# PANOBOT_MAIN_V2.net
KiCad netlist of a schematic drawn in EAGLE
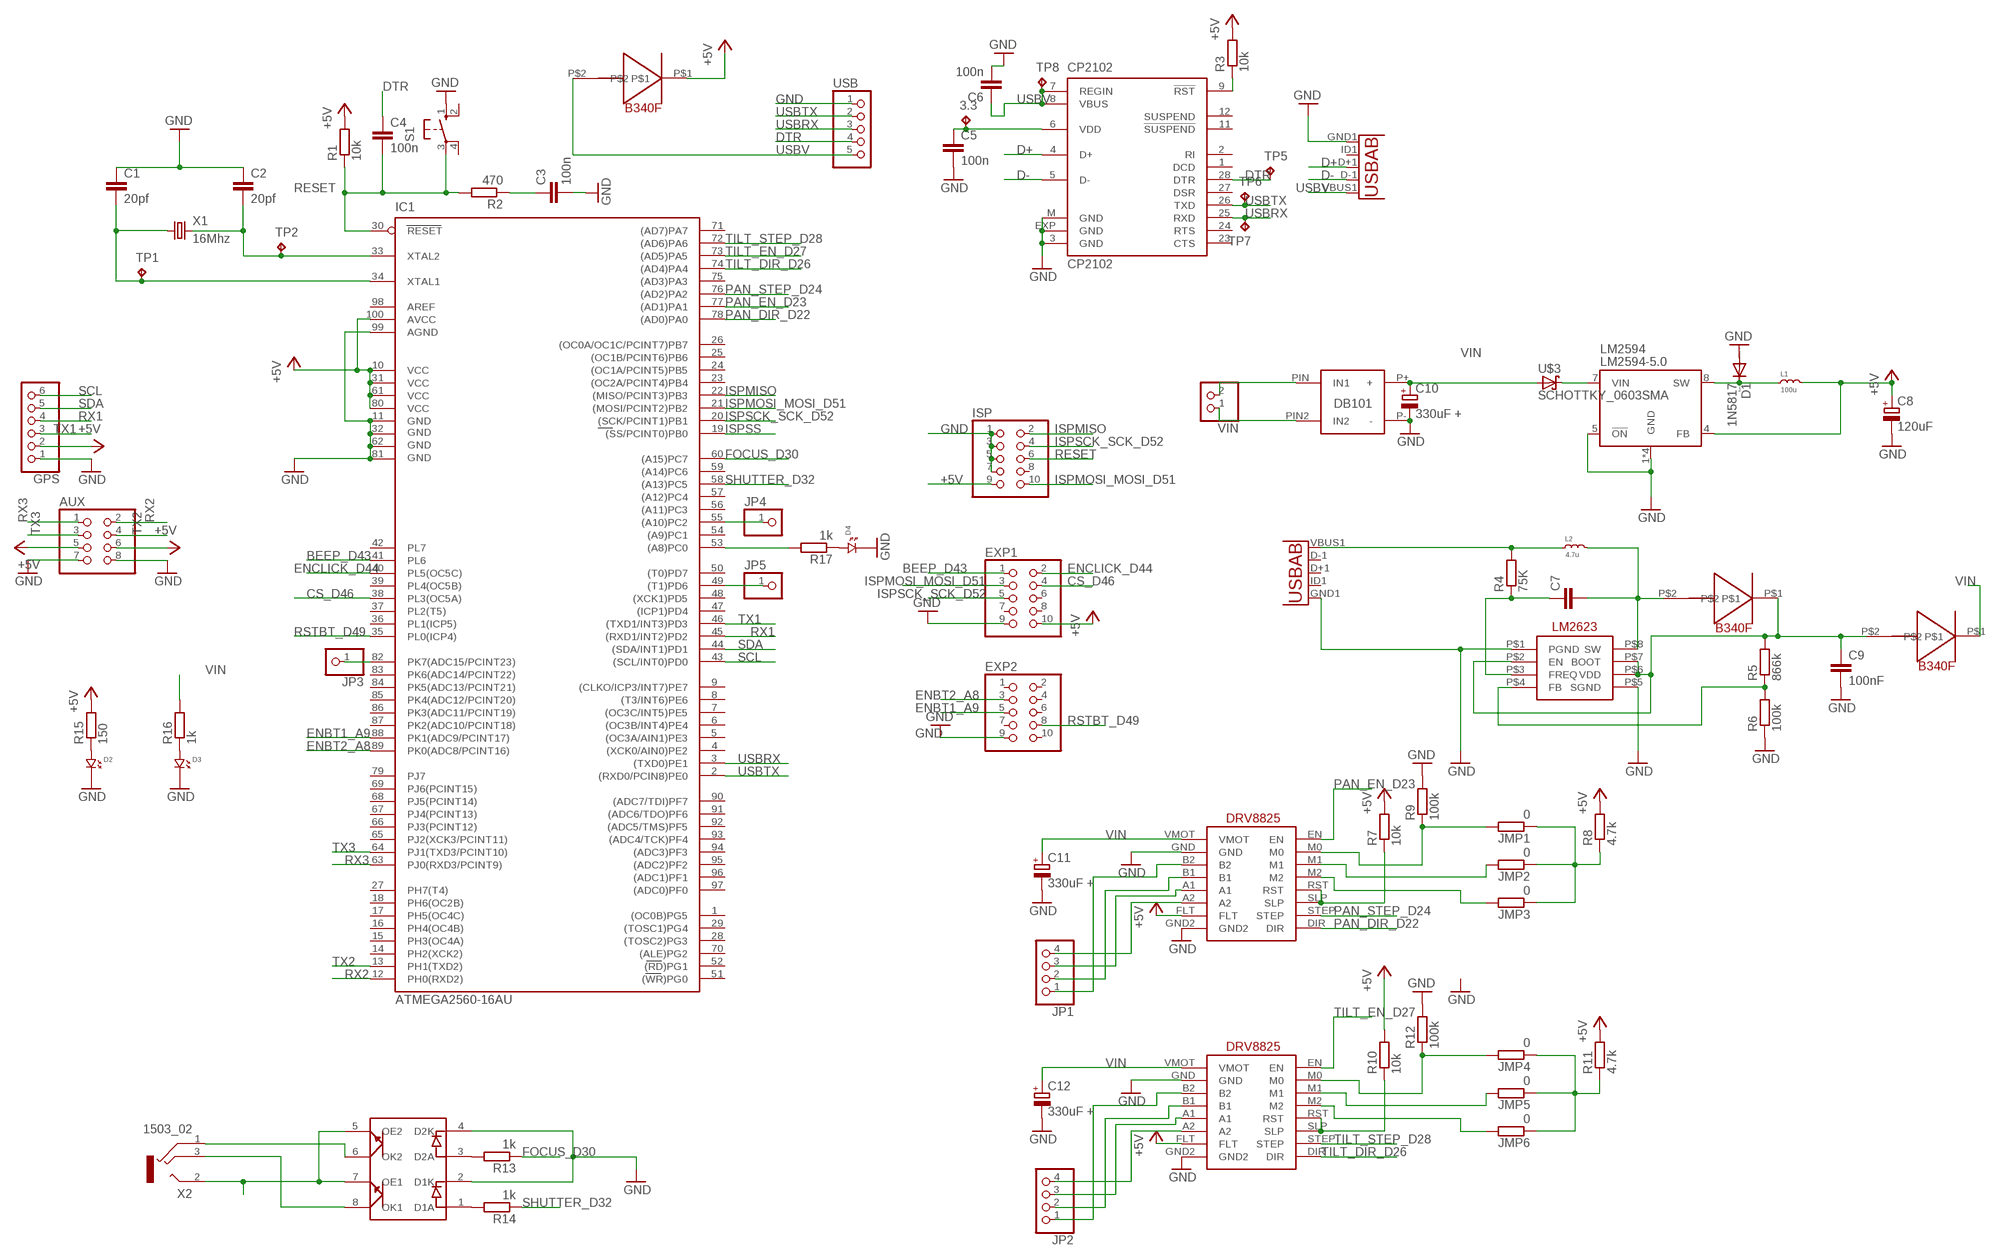
[diagram p0: schematic, sheet 1]

(export (version "E")
  (design (tool "Eeschema 10.0.6"))
  (components
    (comp (ref "3.3")
      (value "TPTP16R")
      (footprint "eagle-import:TP16R")
      (libsource (lib "eagle-import") (part "TPTP16R"))
    )
    (comp (ref "AUX")
      (value "PINHD-2X4")
      (footprint "eagle-import:2X04")
      (libsource (lib "eagle-import") (part "PINHD-2X4"))
    )
    (comp (ref "C1")
      (value "20pf")
      (footprint "eagle-import:C0603K")
      (libsource (lib "eagle-import") (part "C-EUC0603K"))
    )
    (comp (ref "C2")
      (value "20pf")
      (footprint "eagle-import:C0603K")
      (libsource (lib "eagle-import") (part "C-EUC0603K"))
    )
    (comp (ref "C3")
      (value "100n")
      (footprint "eagle-import:C0805")
      (libsource (lib "eagle-import") (part "C-EUC0805"))
    )
    (comp (ref "C4")
      (value "100n")
      (footprint "eagle-import:C0805")
      (libsource (lib "eagle-import") (part "C-EUC0805"))
    )
    (comp (ref "C5")
      (value "100n")
      (footprint "eagle-import:C0805")
      (libsource (lib "eagle-import") (part "C-EUC0805"))
    )
    (comp (ref "C6")
      (value "100n")
      (footprint "eagle-import:C0805")
      (libsource (lib "eagle-import") (part "C-EUC0805"))
    )
    (comp (ref "C7")
      (value "C-EUC0603")
      (footprint "eagle-import:C0603")
      (libsource (lib "eagle-import") (part "C-EUC0603"))
    )
    (comp (ref "C8")
      (value "120uF")
      (footprint "eagle-import:153CLV-0605")
      (libsource (lib "eagle-import") (part "CPOL-EU153CLV-0605"))
    )
    (comp (ref "C9")
      (value "100nF")
      (footprint "eagle-import:C025-030X050")
      (libsource (lib "eagle-import") (part "C-EU025-030X050"))
    )
    (comp (ref "C10")
      (value "330uF +")
      (footprint "eagle-import:SANYO-OSCON_F13")
      (libsource (lib "eagle-import") (part "CPOL-EUSANYO_F13"))
    )
    (comp (ref "C11")
      (value "330uF +")
      (footprint "eagle-import:SANYO-OSCON_F13")
      (libsource (lib "eagle-import") (part "CPOL-EUSANYO_F13"))
    )
    (comp (ref "C12")
      (value "330uF +")
      (footprint "eagle-import:SANYO-OSCON_F13")
      (libsource (lib "eagle-import") (part "CPOL-EUSANYO_F13"))
    )
    (comp (ref "CP2102")
      (value "CP2102")
      (footprint "eagle-import:MLP28")
      (fields (field (name "MF") "FARNELL") (field (name "MPN") "CP2102-GM"))
      (libsource (lib "eagle-import") (part "CP2102"))
    )
    (comp (ref "D1")
      (value "1N5817")
      (footprint "eagle-import:DO41-10")
      (libsource (lib "eagle-import") (part "1N4942"))
    )
    (comp (ref "D2")
      (value "LED.0805")
      (footprint "eagle-import:0805.LED")
      (libsource (lib "eagle-import") (part "LED.0805"))
    )
    (comp (ref "D3")
      (value "LED.0805")
      (footprint "eagle-import:0805.LED")
      (libsource (lib "eagle-import") (part "LED.0805"))
    )
    (comp (ref "D4")
      (value "LED.0805")
      (footprint "eagle-import:0805.LED")
      (libsource (lib "eagle-import") (part "LED.0805"))
    )
    (comp (ref "EXP1")
      (value "PINHD-2X5")
      (footprint "eagle-import:2X05")
      (libsource (lib "eagle-import") (part "PINHD-2X5"))
    )
    (comp (ref "EXP2")
      (value "PINHD-2X5")
      (footprint "eagle-import:2X05")
      (libsource (lib "eagle-import") (part "PINHD-2X5"))
    )
    (comp (ref "GPS")
      (value "PINHD-1X6")
      (footprint "eagle-import:1X06")
      (libsource (lib "eagle-import") (part "PINHD-1X6"))
    )
    (comp (ref "IC1")
      (value "ATMEGA2560-16AU")
      (footprint "eagle-import:TQFP100")
      (libsource (lib "eagle-import") (part "ATMEGAAU2560-16"))
    )
    (comp (ref "ISP")
      (value "PINHD-2X5")
      (footprint "eagle-import:2X05")
      (libsource (lib "eagle-import") (part "PINHD-2X5"))
    )
    (comp (ref "JMP1")
      (value "0")
      (footprint "eagle-import:R0805")
      (libsource (lib "eagle-import") (part "R-EU_R0805"))
    )
    (comp (ref "JMP2")
      (value "0")
      (footprint "eagle-import:R0805")
      (libsource (lib "eagle-import") (part "R-EU_R0805"))
    )
    (comp (ref "JMP3")
      (value "0")
      (footprint "eagle-import:R0805")
      (libsource (lib "eagle-import") (part "R-EU_R0805"))
    )
    (comp (ref "JMP4")
      (value "0")
      (footprint "eagle-import:R0805")
      (libsource (lib "eagle-import") (part "R-EU_R0805"))
    )
    (comp (ref "JMP5")
      (value "0")
      (footprint "eagle-import:R0805")
      (libsource (lib "eagle-import") (part "R-EU_R0805"))
    )
    (comp (ref "JMP6")
      (value "0")
      (footprint "eagle-import:R0805")
      (libsource (lib "eagle-import") (part "R-EU_R0805"))
    )
    (comp (ref "JP1")
      (value "PINHD-1X4")
      (footprint "eagle-import:1X04")
      (libsource (lib "eagle-import") (part "PINHD-1X4"))
    )
    (comp (ref "JP2")
      (value "PINHD-1X4")
      (footprint "eagle-import:1X04")
      (libsource (lib "eagle-import") (part "PINHD-1X4"))
    )
    (comp (ref "JP3")
      (value "PINHD-1X1")
      (footprint "eagle-import:1X01")
      (libsource (lib "eagle-import") (part "PINHD-1X1"))
    )
    (comp (ref "JP4")
      (value "PINHD-1X1")
      (footprint "eagle-import:1X01")
      (libsource (lib "eagle-import") (part "PINHD-1X1"))
    )
    (comp (ref "JP5")
      (value "PINHD-1X1")
      (footprint "eagle-import:1X01")
      (libsource (lib "eagle-import") (part "PINHD-1X1"))
    )
    (comp (ref "L1")
      (value "100u")
      (footprint "eagle-import:HPINDUCTOR100")
      (libsource (lib "eagle-import") (part "RF-INDUCTOR.HP100"))
    )
    (comp (ref "L2")
      (value "4.7u")
      (footprint "eagle-import:HPINDUCOR")
      (libsource (lib "eagle-import") (part "RF-INDUCTOR"))
    )
    (comp (ref "LM2594")
      (value "LM2594-5.0")
      (footprint "eagle-import:SO08")
      (libsource (lib "eagle-import") (part "LM2594-5.0"))
    )
    (comp (ref "LM2623")
      (value "LM2623")
      (footprint "eagle-import:MINI-SO-8")
      (libsource (lib "eagle-import") (part "LM2623"))
    )
    (comp (ref "R1")
      (value "10k")
      (footprint "eagle-import:R0805")
      (libsource (lib "eagle-import") (part "R-EU_R0805"))
    )
    (comp (ref "R2")
      (value "470")
      (footprint "eagle-import:R0805")
      (libsource (lib "eagle-import") (part "R-EU_R0805"))
    )
    (comp (ref "R3")
      (value "10k")
      (footprint "eagle-import:R0805")
      (libsource (lib "eagle-import") (part "R-EU_R0805"))
    )
    (comp (ref "R4")
      (value "75K")
      (footprint "eagle-import:R0805")
      (libsource (lib "eagle-import") (part "R-EU_R0805"))
    )
    (comp (ref "R5")
      (value "866k")
      (footprint "eagle-import:R0805")
      (libsource (lib "eagle-import") (part "R-EU_R0805"))
    )
    (comp (ref "R6")
      (value "100k")
      (footprint "eagle-import:R0805")
      (libsource (lib "eagle-import") (part "R-EU_R0805"))
    )
    (comp (ref "R7")
      (value "10k")
      (footprint "eagle-import:R0805")
      (libsource (lib "eagle-import") (part "R-EU_R0805"))
    )
    (comp (ref "R8")
      (value "4.7k")
      (footprint "eagle-import:R0805")
      (libsource (lib "eagle-import") (part "R-EU_R0805"))
    )
    (comp (ref "R9")
      (value "100k")
      (footprint "eagle-import:R0805")
      (libsource (lib "eagle-import") (part "R-EU_R0805"))
    )
    (comp (ref "R10")
      (value "10k")
      (footprint "eagle-import:R0805")
      (libsource (lib "eagle-import") (part "R-EU_R0805"))
    )
    (comp (ref "R11")
      (value "4.7k")
      (footprint "eagle-import:R0805")
      (libsource (lib "eagle-import") (part "R-EU_R0805"))
    )
    (comp (ref "R12")
      (value "100k")
      (footprint "eagle-import:R0805")
      (libsource (lib "eagle-import") (part "R-EU_R0805"))
    )
    (comp (ref "R13")
      (value "1k")
      (footprint "eagle-import:R0805")
      (libsource (lib "eagle-import") (part "R-EU_R0805"))
    )
    (comp (ref "R14")
      (value "1k")
      (footprint "eagle-import:R0805")
      (libsource (lib "eagle-import") (part "R-EU_R0805"))
    )
    (comp (ref "R15")
      (value "150")
      (footprint "eagle-import:R0805")
      (libsource (lib "eagle-import") (part "R-EU_R0805"))
    )
    (comp (ref "R16")
      (value "1k")
      (footprint "eagle-import:R0805")
      (libsource (lib "eagle-import") (part "R-EU_R0805"))
    )
    (comp (ref "R17")
      (value "1k")
      (footprint "eagle-import:R0805")
      (libsource (lib "eagle-import") (part "R-EU_R0805"))
    )
    (comp (ref "S1")
      (value "10-XX")
      (footprint "eagle-import:B3F-10XX")
      (fields (field (name "MPN") "B3F-1000"))
      (libsource (lib "eagle-import") (part "10-XX"))
    )
    (comp (ref "TP1")
      (value "TPTP16R")
      (footprint "eagle-import:TP16R")
      (libsource (lib "eagle-import") (part "TPTP16R"))
    )
    (comp (ref "TP2")
      (value "TPTP16R")
      (footprint "eagle-import:TP16R")
      (libsource (lib "eagle-import") (part "TPTP16R"))
    )
    (comp (ref "TP5")
      (value "TPTP16R")
      (footprint "eagle-import:TP16R")
      (libsource (lib "eagle-import") (part "TPTP16R"))
    )
    (comp (ref "TP6")
      (value "TPTP16R")
      (footprint "eagle-import:TP16R")
      (libsource (lib "eagle-import") (part "TPTP16R"))
    )
    (comp (ref "TP7")
      (value "TPTP16R")
      (footprint "eagle-import:TP16R")
      (libsource (lib "eagle-import") (part "TPTP16R"))
    )
    (comp (ref "TP8")
      (value "TPTP16R")
      (footprint "eagle-import:TP16R")
      (libsource (lib "eagle-import") (part "TPTP16R"))
    )
    (comp (ref "U$1")
      (value "B340FSCHOTTKY")
      (footprint "eagle-import:SMC")
      (libsource (lib "eagle-import") (part "B340FSCHOTTKY"))
    )
    (comp (ref "U$2")
      (value "DB101_BRUECKENGLEICHRICHTER")
      (footprint "eagle-import:DB101_PACK")
      (libsource (lib "eagle-import") (part "DB101_BRUECKENGLEICHRICHTER"))
    )
    (comp (ref "U$3")
      (value "SCHOTTKY_0603SMA")
      (footprint "eagle-import:SMA")
      (libsource (lib "eagle-import") (part "SCHOTTKY_0603SMA"))
    )
    (comp (ref "U$4")
      (value "B340FSCHOTTKY")
      (footprint "eagle-import:SMC")
      (libsource (lib "eagle-import") (part "B340FSCHOTTKY"))
    )
    (comp (ref "U$5")
      (value "B340FSCHOTTKY")
      (footprint "eagle-import:SMC")
      (libsource (lib "eagle-import") (part "B340FSCHOTTKY"))
    )
    (comp (ref "U$6")
      (value "DRV8825")
      (footprint "eagle-import:DRV8825POLULOU")
      (libsource (lib "eagle-import") (part "DRV8825"))
    )
    (comp (ref "U$7")
      (value "DRV8825")
      (footprint "eagle-import:DRV8825POLULOU")
      (libsource (lib "eagle-import") (part "DRV8825"))
    )
    (comp (ref "U$8")
      (value "LTV827SMD8")
      (footprint "eagle-import:SMD8")
      (fields (field (name "SPICEPREFIX") "X"))
      (libsource (lib "eagle-import") (part "LTV827SMD8"))
    )
    (comp (ref "U1")
      (value "USB\"\"")
      (footprint "eagle-import:USB-MICRO-SMD")
      (libsource (lib "eagle-import") (part "USB{dblquote}{dblquote}"))
    )
    (comp (ref "U2")
      (value "USB\"\"")
      (footprint "eagle-import:USB-MICRO-SMD")
      (libsource (lib "eagle-import") (part "USB{dblquote}{dblquote}"))
    )
    (comp (ref "USB")
      (value "PINHD-1X5")
      (footprint "eagle-import:1X05")
      (libsource (lib "eagle-import") (part "PINHD-1X5"))
    )
    (comp (ref "VIN")
      (value "PINHD-1X2")
      (footprint "eagle-import:1X02")
      (libsource (lib "eagle-import") (part "PINHD-1X2"))
    )
    (comp (ref "X1")
      (value "16Mhz")
      (footprint "eagle-import:HC49-4-HSMX")
      (libsource (lib "eagle-import") (part "CRYSTALS-NOGND-4-HSMX"))
    )
    (comp (ref "X2")
      (value "1503_02")
      (footprint "eagle-import:1503_02")
      (libsource (lib "eagle-import") (part "1503_02"))
    )
  )
  (nets
    (net (code "1") (name "+5V") (class "Default")
      (node (ref "AUX") (pin "5") (pinfunction "5_5") (pintype "passive"))
      (node (ref "AUX") (pin "6") (pinfunction "6_6") (pintype "passive"))
      (node (ref "C8") (pin "+") (pinfunction "+_+") (pintype "passive"))
      (node (ref "EXP1") (pin "10") (pinfunction "10_10") (pintype "passive"))
      (node (ref "GPS") (pin "2") (pinfunction "2_2") (pintype "passive"))
      (node (ref "IC1") (pin "10") (pinfunction "VCC_10") (pintype "power_in"))
      (node (ref "IC1") (pin "100") (pinfunction "AVCC_100") (pintype "power_in"))
      (node (ref "IC1") (pin "31") (pinfunction "VCC1_31") (pintype "power_in"))
      (node (ref "IC1") (pin "61") (pinfunction "VCC2_61") (pintype "power_in"))
      (node (ref "IC1") (pin "80") (pinfunction "VCC3_80") (pintype "power_in"))
      (node (ref "ISP") (pin "9") (pinfunction "9_9") (pintype "passive"))
      (node (ref "L1") (pin "P$2") (pinfunction "2_P$2") (pintype "passive"))
      (node (ref "LM2594") (pin "4") (pinfunction "FB_4") (pintype "passive"))
      (node (ref "R1") (pin "2") (pinfunction "2_2") (pintype "passive"))
      (node (ref "R10") (pin "2") (pinfunction "2_2") (pintype "passive"))
      (node (ref "R11") (pin "2") (pinfunction "2_2") (pintype "passive"))
      (node (ref "R15") (pin "2") (pinfunction "2_2") (pintype "passive"))
      (node (ref "R3") (pin "2") (pinfunction "2_2") (pintype "passive"))
      (node (ref "R7") (pin "2") (pinfunction "2_2") (pintype "passive"))
      (node (ref "R8") (pin "2") (pinfunction "2_2") (pintype "passive"))
      (node (ref "U$1") (pin "P$1") (pinfunction "P$1_P$1") (pintype "bidirectional"))
      (node (ref "U$6") (pin "FLT") (pinfunction "FLT_FLT") (pintype "bidirectional"))
      (node (ref "U$7") (pin "FLT") (pinfunction "FLT_FLT") (pintype "bidirectional"))
    )
    (net (code "2") (name "/BEEP_D43") (class "Default")
      (node (ref "EXP1") (pin "1") (pinfunction "1_1") (pintype "passive"))
      (node (ref "IC1") (pin "41") (pinfunction "PL6_41") (pintype "bidirectional"))
    )
    (net (code "3") (name "/CS_D46") (class "Default")
      (node (ref "EXP1") (pin "4") (pinfunction "4_4") (pintype "passive"))
      (node (ref "IC1") (pin "38") (pinfunction "PL3(OC5A)_38") (pintype "bidirectional"))
    )
    (net (code "4") (name "/D+") (class "Default")
      (node (ref "CP2102") (pin "4") (pinfunction "D+_4") (pintype "bidirectional"))
      (node (ref "U1") (pin "D+1") (pinfunction "D+_D+1") (pintype "bidirectional"))
    )
    (net (code "5") (name "/D-") (class "Default")
      (node (ref "CP2102") (pin "5") (pinfunction "D-_5") (pintype "bidirectional"))
      (node (ref "U1") (pin "D-1") (pinfunction "D-_D-1") (pintype "bidirectional"))
    )
    (net (code "6") (name "/DTR") (class "Default")
      (node (ref "C4") (pin "1") (pinfunction "1_1") (pintype "passive"))
      (node (ref "CP2102") (pin "28") (pinfunction "DTR_28") (pintype "output"))
      (node (ref "TP5") (pin "TP") (pinfunction "TP_TP") (pintype "input"))
      (node (ref "USB") (pin "4") (pinfunction "4_4") (pintype "passive"))
    )
    (net (code "7") (name "/ENBT1_A9") (class "Default")
      (node (ref "EXP2") (pin "5") (pinfunction "5_5") (pintype "passive"))
      (node (ref "IC1") (pin "88") (pinfunction "PK1(ADC9/PCINT17)_88") (pintype "bidirectional"))
    )
    (net (code "8") (name "/ENBT2_A8") (class "Default")
      (node (ref "EXP2") (pin "3") (pinfunction "3_3") (pintype "passive"))
      (node (ref "IC1") (pin "89") (pinfunction "PK0(ADC8/PCINT16)_89") (pintype "bidirectional"))
    )
    (net (code "9") (name "/ENCLICK_D44") (class "Default")
      (node (ref "EXP1") (pin "2") (pinfunction "2_2") (pintype "passive"))
      (node (ref "IC1") (pin "40") (pinfunction "PL5(OC5C)_40") (pintype "bidirectional"))
    )
    (net (code "10") (name "/FOCUS_D30") (class "Default")
      (node (ref "IC1") (pin "60") (pinfunction "(A15)PC7_60") (pintype "bidirectional"))
      (node (ref "R13") (pin "1") (pinfunction "1_1") (pintype "passive"))
    )
    (net (code "11") (name "/ISPMISO") (class "Default")
      (node (ref "IC1") (pin "22") (pinfunction "(MISO/PCINT3)PB3_22") (pintype "bidirectional"))
      (node (ref "ISP") (pin "2") (pinfunction "2_2") (pintype "passive"))
    )
    (net (code "12") (name "/ISPMOSI_MOSI_D51") (class "Default")
      (node (ref "EXP1") (pin "3") (pinfunction "3_3") (pintype "passive"))
      (node (ref "IC1") (pin "21") (pinfunction "(MOSI/PCINT2)PB2_21") (pintype "bidirectional"))
      (node (ref "ISP") (pin "10") (pinfunction "10_10") (pintype "passive"))
    )
    (net (code "13") (name "/ISPSCK_SCK_D52") (class "Default")
      (node (ref "EXP1") (pin "5") (pinfunction "5_5") (pintype "passive"))
      (node (ref "IC1") (pin "20") (pinfunction "(SCK/PCINT1)PB1_20") (pintype "bidirectional"))
      (node (ref "ISP") (pin "4") (pinfunction "4_4") (pintype "passive"))
    )
    (net (code "14") (name "/ISPSS") (class "Default")
      (node (ref "IC1") (pin "19") (pinfunction "(SS/PCINT0)PB0_19") (pintype "bidirectional"))
    )
    (net (code "15") (name "/PAN_DIR_D22") (class "Default")
      (node (ref "IC1") (pin "78") (pinfunction "(AD0)PA0_78") (pintype "bidirectional"))
      (node (ref "U$6") (pin "DIR") (pinfunction "DIR_DIR") (pintype "bidirectional"))
    )
    (net (code "16") (name "/PAN_EN_D23") (class "Default")
      (node (ref "IC1") (pin "77") (pinfunction "(AD1)PA1_77") (pintype "bidirectional"))
      (node (ref "U$6") (pin "EN") (pinfunction "EN_EN") (pintype "bidirectional"))
    )
    (net (code "17") (name "/PAN_STEP_D24") (class "Default")
      (node (ref "IC1") (pin "76") (pinfunction "(AD2)PA2_76") (pintype "bidirectional"))
      (node (ref "U$6") (pin "STEP") (pinfunction "STEP_STEP") (pintype "bidirectional"))
    )
    (net (code "18") (name "/RESET") (class "Default")
      (node (ref "C4") (pin "2") (pinfunction "2_2") (pintype "passive"))
      (node (ref "IC1") (pin "30") (pinfunction "RESET_30") (pintype "input"))
      (node (ref "ISP") (pin "6") (pinfunction "6_6") (pintype "passive"))
      (node (ref "R1") (pin "1") (pinfunction "1_1") (pintype "passive"))
      (node (ref "R2") (pin "2") (pinfunction "2_2") (pintype "passive"))
      (node (ref "S1") (pin "3") (pinfunction "P_3") (pintype "passive"))
    )
    (net (code "19") (name "/RSTBT_D49") (class "Default")
      (node (ref "EXP2") (pin "8") (pinfunction "8_8") (pintype "passive"))
      (node (ref "IC1") (pin "35") (pinfunction "PL0(ICP4)_35") (pintype "bidirectional"))
    )
    (net (code "20") (name "/RX1") (class "Default")
      (node (ref "GPS") (pin "4") (pinfunction "4_4") (pintype "passive"))
      (node (ref "IC1") (pin "45") (pinfunction "(RXD1/INT2)PD2_45") (pintype "bidirectional"))
    )
    (net (code "21") (name "/RX2") (class "Default")
      (node (ref "AUX") (pin "2") (pinfunction "2_2") (pintype "passive"))
      (node (ref "IC1") (pin "12") (pinfunction "PH0(RXD2)_12") (pintype "bidirectional"))
    )
    (net (code "22") (name "/RX3") (class "Default")
      (node (ref "AUX") (pin "1") (pinfunction "1_1") (pintype "passive"))
      (node (ref "IC1") (pin "63") (pinfunction "PJ0(RXD3/PCINT9)_63") (pintype "bidirectional"))
    )
    (net (code "23") (name "/SCL") (class "Default")
      (node (ref "GPS") (pin "6") (pinfunction "6_6") (pintype "passive"))
      (node (ref "IC1") (pin "43") (pinfunction "(SCL/INT0)PD0_43") (pintype "bidirectional"))
    )
    (net (code "24") (name "/SDA") (class "Default")
      (node (ref "GPS") (pin "5") (pinfunction "5_5") (pintype "passive"))
      (node (ref "IC1") (pin "44") (pinfunction "(SDA/INT1)PD1_44") (pintype "bidirectional"))
    )
    (net (code "25") (name "/SHUTTER_D32") (class "Default")
      (node (ref "IC1") (pin "58") (pinfunction "(A13)PC5_58") (pintype "bidirectional"))
      (node (ref "R14") (pin "1") (pinfunction "1_1") (pintype "passive"))
    )
    (net (code "26") (name "/TILT_DIR_D26") (class "Default")
      (node (ref "IC1") (pin "74") (pinfunction "(AD4)PA4_74") (pintype "bidirectional"))
      (node (ref "U$7") (pin "DIR") (pinfunction "DIR_DIR") (pintype "bidirectional"))
    )
    (net (code "27") (name "/TILT_EN_D27") (class "Default")
      (node (ref "IC1") (pin "73") (pinfunction "(AD5)PA5_73") (pintype "bidirectional"))
      (node (ref "U$7") (pin "EN") (pinfunction "EN_EN") (pintype "bidirectional"))
    )
    (net (code "28") (name "/TILT_STEP_D28") (class "Default")
      (node (ref "IC1") (pin "72") (pinfunction "(AD6)PA6_72") (pintype "bidirectional"))
      (node (ref "U$7") (pin "STEP") (pinfunction "STEP_STEP") (pintype "bidirectional"))
    )
    (net (code "29") (name "/TX1") (class "Default")
      (node (ref "GPS") (pin "3") (pinfunction "3_3") (pintype "passive"))
      (node (ref "IC1") (pin "46") (pinfunction "(TXD1/INT3)PD3_46") (pintype "bidirectional"))
    )
    (net (code "30") (name "/TX2") (class "Default")
      (node (ref "AUX") (pin "4") (pinfunction "4_4") (pintype "passive"))
      (node (ref "IC1") (pin "13") (pinfunction "PH1(TXD2)_13") (pintype "bidirectional"))
    )
    (net (code "31") (name "/TX3") (class "Default")
      (node (ref "AUX") (pin "3") (pinfunction "3_3") (pintype "passive"))
      (node (ref "IC1") (pin "64") (pinfunction "PJ1(TXD3/PCINT10)_64") (pintype "bidirectional"))
    )
    (net (code "32") (name "/USBRX") (class "Default")
      (node (ref "CP2102") (pin "25") (pinfunction "RXD_25") (pintype "input"))
      (node (ref "IC1") (pin "3") (pinfunction "(TXD0)PE1_3") (pintype "bidirectional"))
      (node (ref "TP7") (pin "TP") (pinfunction "TP_TP") (pintype "input"))
      (node (ref "USB") (pin "3") (pinfunction "3_3") (pintype "passive"))
    )
    (net (code "33") (name "/USBTX") (class "Default")
      (node (ref "CP2102") (pin "26") (pinfunction "TXD_26") (pintype "output"))
      (node (ref "IC1") (pin "2") (pinfunction "(RXD0/PCIN8)PE0_2") (pintype "bidirectional"))
      (node (ref "TP6") (pin "TP") (pinfunction "TP_TP") (pintype "input"))
      (node (ref "USB") (pin "2") (pinfunction "2_2") (pintype "passive"))
    )
    (net (code "34") (name "/USBV") (class "Default")
      (node (ref "C6") (pin "1") (pinfunction "1_1") (pintype "passive"))
      (node (ref "CP2102") (pin "7") (pinfunction "REGIN_7") (pintype "passive"))
      (node (ref "CP2102") (pin "8") (pinfunction "VBUS_8") (pintype "input"))
      (node (ref "TP8") (pin "TP") (pinfunction "TP_TP") (pintype "input"))
      (node (ref "U$1") (pin "P$2") (pinfunction "P$2_P$2") (pintype "bidirectional"))
      (node (ref "U1") (pin "VBUS1") (pinfunction "VBUS_VBUS1") (pintype "bidirectional"))
      (node (ref "USB") (pin "5") (pinfunction "5_5") (pintype "passive"))
    )
    (net (code "35") (name "/VIN") (class "Default")
      (node (ref "C10") (pin "+") (pinfunction "+_+") (pintype "passive"))
      (node (ref "C11") (pin "+") (pinfunction "+_+") (pintype "passive"))
      (node (ref "C12") (pin "+") (pinfunction "+_+") (pintype "passive"))
      (node (ref "R16") (pin "2") (pinfunction "2_2") (pintype "passive"))
      (node (ref "U$2") (pin "P+") (pinfunction "+_P+") (pintype "bidirectional"))
      (node (ref "U$3") (pin "P$2") (pinfunction "A_P$2") (pintype "passive"))
      (node (ref "U$5") (pin "P$1") (pinfunction "P$1_P$1") (pintype "bidirectional"))
      (node (ref "U$6") (pin "VMOT") (pinfunction "VMOT_VMOT") (pintype "bidirectional"))
      (node (ref "U$7") (pin "VMOT") (pinfunction "VMOT_VMOT") (pintype "bidirectional"))
    )
    (net (code "36") (name "GND") (class "Default")
      (node (ref "AUX") (pin "7") (pinfunction "7_7") (pintype "passive"))
      (node (ref "AUX") (pin "8") (pinfunction "8_8") (pintype "passive"))
      (node (ref "C1") (pin "1") (pinfunction "1_1") (pintype "passive"))
      (node (ref "C10") (pin "-") (pinfunction "-_-") (pintype "passive"))
      (node (ref "C11") (pin "-") (pinfunction "-_-") (pintype "passive"))
      (node (ref "C12") (pin "-") (pinfunction "-_-") (pintype "passive"))
      (node (ref "C2") (pin "1") (pinfunction "1_1") (pintype "passive"))
      (node (ref "C3") (pin "2") (pinfunction "2_2") (pintype "passive"))
      (node (ref "C5") (pin "2") (pinfunction "2_2") (pintype "passive"))
      (node (ref "C6") (pin "2") (pinfunction "2_2") (pintype "passive"))
      (node (ref "C8") (pin "-") (pinfunction "-_-") (pintype "passive"))
      (node (ref "C9") (pin "2") (pinfunction "2_2") (pintype "passive"))
      (node (ref "CP2102") (pin "3") (pinfunction "GND_3") (pintype "power_in"))
      (node (ref "CP2102") (pin "EXP") (pinfunction "GND_EXP") (pintype "power_in"))
      (node (ref "CP2102") (pin "M") (pinfunction "GND_M") (pintype "power_in"))
      (node (ref "D1") (pin "A") (pinfunction "A_A") (pintype "passive"))
      (node (ref "D2") (pin "P$2") (pinfunction "2_P$2") (pintype "bidirectional"))
      (node (ref "D3") (pin "P$2") (pinfunction "2_P$2") (pintype "bidirectional"))
      (node (ref "D4") (pin "P$2") (pinfunction "2_P$2") (pintype "bidirectional"))
      (node (ref "EXP1") (pin "9") (pinfunction "9_9") (pintype "passive"))
      (node (ref "EXP2") (pin "9") (pinfunction "9_9") (pintype "passive"))
      (node (ref "GPS") (pin "1") (pinfunction "1_1") (pintype "passive"))
      (node (ref "IC1") (pin "11") (pinfunction "GND_11") (pintype "power_in"))
      (node (ref "IC1") (pin "32") (pinfunction "GND1_32") (pintype "power_in"))
      (node (ref "IC1") (pin "62") (pinfunction "GND2_62") (pintype "power_in"))
      (node (ref "IC1") (pin "81") (pinfunction "GND3_81") (pintype "power_in"))
      (node (ref "IC1") (pin "99") (pinfunction "AGND_99") (pintype "power_in"))
      (node (ref "ISP") (pin "1") (pinfunction "1_1") (pintype "passive"))
      (node (ref "ISP") (pin "3") (pinfunction "3_3") (pintype "passive"))
      (node (ref "ISP") (pin "5") (pinfunction "5_5") (pintype "passive"))
      (node (ref "ISP") (pin "7") (pinfunction "7_7") (pintype "passive"))
      (node (ref "LM2594") (pin "1") (pinfunction "GND_1") (pintype "power_in"))
      (node (ref "LM2594") (pin "2") (pinfunction "GND_2") (pintype "power_in"))
      (node (ref "LM2594") (pin "3") (pinfunction "GND_3") (pintype "power_in"))
      (node (ref "LM2594") (pin "5") (pinfunction "~{ON}_5") (pintype "input"))
      (node (ref "LM2594") (pin "6") (pinfunction "GND_6") (pintype "power_in"))
      (node (ref "LM2623") (pin "P$1") (pinfunction "PGND_P$1") (pintype "bidirectional"))
      (node (ref "LM2623") (pin "P$5") (pinfunction "SGND_P$5") (pintype "bidirectional"))
      (node (ref "R12") (pin "2") (pinfunction "2_2") (pintype "passive"))
      (node (ref "R6") (pin "1") (pinfunction "1_1") (pintype "passive"))
      (node (ref "R9") (pin "2") (pinfunction "2_2") (pintype "passive"))
      (node (ref "S1") (pin "1") (pinfunction "S_1") (pintype "passive"))
      (node (ref "U$2") (pin "P-") (pinfunction "-_P-") (pintype "bidirectional"))
      (node (ref "U$6") (pin "GND") (pinfunction "GND_GND") (pintype "bidirectional"))
      (node (ref "U$6") (pin "GND2") (pinfunction "GND2_GND2") (pintype "bidirectional"))
      (node (ref "U$7") (pin "GND") (pinfunction "GND_GND") (pintype "bidirectional"))
      (node (ref "U$7") (pin "GND2") (pinfunction "GND2_GND2") (pintype "bidirectional"))
      (node (ref "U$8") (pin "2") (pinfunction "D1K_2") (pintype "bidirectional"))
      (node (ref "U$8") (pin "4") (pinfunction "D2K_4") (pintype "bidirectional"))
      (node (ref "U1") (pin "GND1") (pinfunction "GND_GND1") (pintype "bidirectional"))
      (node (ref "U2") (pin "GND1") (pinfunction "GND_GND1") (pintype "bidirectional"))
      (node (ref "USB") (pin "1") (pinfunction "1_1") (pintype "passive"))
    )
    (net (code "37") (name "Net-(C3-Pad1)") (class "Default")
      (node (ref "C3") (pin "1") (pinfunction "1_1") (pintype "passive"))
      (node (ref "R2") (pin "1") (pinfunction "1_1") (pintype "passive"))
    )
    (net (code "38") (name "Net-(CP2102-VDD)") (class "Default")
      (node (ref "3.3") (pin "TP") (pinfunction "TP_TP") (pintype "input"))
      (node (ref "C5") (pin "1") (pinfunction "1_1") (pintype "passive"))
      (node (ref "CP2102") (pin "6") (pinfunction "VDD_6") (pintype "power_in"))
    )
    (net (code "39") (name "Net-(CP2102-~{RST})") (class "Default")
      (node (ref "CP2102") (pin "9") (pinfunction "~{RST}_9") (pintype "bidirectional"))
      (node (ref "R3") (pin "1") (pinfunction "1_1") (pintype "passive"))
    )
    (net (code "40") (name "Net-(D2-1)") (class "Default")
      (node (ref "D2") (pin "P$1") (pinfunction "1_P$1") (pintype "bidirectional"))
      (node (ref "R15") (pin "1") (pinfunction "1_1") (pintype "passive"))
    )
    (net (code "41") (name "Net-(D3-1)") (class "Default")
      (node (ref "D3") (pin "P$1") (pinfunction "1_P$1") (pintype "bidirectional"))
      (node (ref "R16") (pin "1") (pinfunction "1_1") (pintype "passive"))
    )
    (net (code "42") (name "Net-(D4-1)") (class "Default")
      (node (ref "D4") (pin "P$1") (pinfunction "1_P$1") (pintype "bidirectional"))
      (node (ref "R17") (pin "1") (pinfunction "1_1") (pintype "passive"))
    )
    (net (code "43") (name "Net-(IC1-(A8)PC0)") (class "Default")
      (node (ref "IC1") (pin "53") (pinfunction "(A8)PC0_53") (pintype "bidirectional"))
      (node (ref "R17") (pin "2") (pinfunction "2_2") (pintype "passive"))
    )
    (net (code "44") (name "Net-(IC1-(A10)PC2)") (class "Default")
      (node (ref "IC1") (pin "55") (pinfunction "(A10)PC2_55") (pintype "bidirectional"))
      (node (ref "JP4") (pin "1") (pinfunction "1_1") (pintype "passive"))
    )
    (net (code "45") (name "Net-(IC1-(T1)PD6)") (class "Default")
      (node (ref "IC1") (pin "49") (pinfunction "(T1)PD6_49") (pintype "bidirectional"))
      (node (ref "JP5") (pin "1") (pinfunction "1_1") (pintype "passive"))
    )
    (net (code "46") (name "Net-(IC1-PK7(ADC15{slash}PCINT23))") (class "Default")
      (node (ref "IC1") (pin "82") (pinfunction "PK7(ADC15/PCINT23)_82") (pintype "bidirectional"))
      (node (ref "JP3") (pin "1") (pinfunction "1_1") (pintype "passive"))
    )
    (net (code "47") (name "Net-(IC1-XTAL1)") (class "Default")
      (node (ref "C1") (pin "2") (pinfunction "2_2") (pintype "passive"))
      (node (ref "IC1") (pin "34") (pinfunction "XTAL1_34") (pintype "input"))
      (node (ref "TP1") (pin "TP") (pinfunction "TP_TP") (pintype "input"))
      (node (ref "X1") (pin "1") (pinfunction "1_1") (pintype "passive"))
    )
    (net (code "48") (name "Net-(IC1-XTAL2)") (class "Default")
      (node (ref "C2") (pin "2") (pinfunction "2_2") (pintype "passive"))
      (node (ref "IC1") (pin "33") (pinfunction "XTAL2_33") (pintype "output"))
      (node (ref "TP2") (pin "TP") (pinfunction "TP_TP") (pintype "input"))
      (node (ref "X1") (pin "2") (pinfunction "2_2") (pintype "passive"))
    )
    (net (code "49") (name "Net-(JMP1-Pad1)") (class "Default")
      (node (ref "JMP1") (pin "1") (pinfunction "1_1") (pintype "passive"))
      (node (ref "JMP2") (pin "1") (pinfunction "1_1") (pintype "passive"))
      (node (ref "JMP3") (pin "1") (pinfunction "1_1") (pintype "passive"))
      (node (ref "R8") (pin "1") (pinfunction "1_1") (pintype "passive"))
    )
    (net (code "50") (name "Net-(JMP1-Pad2)") (class "Default")
      (node (ref "JMP1") (pin "2") (pinfunction "2_2") (pintype "passive"))
      (node (ref "R9") (pin "1") (pinfunction "1_1") (pintype "passive"))
      (node (ref "U$6") (pin "M0") (pinfunction "M0_M0") (pintype "bidirectional"))
    )
    (net (code "51") (name "Net-(JMP2-Pad2)") (class "Default")
      (node (ref "JMP2") (pin "2") (pinfunction "2_2") (pintype "passive"))
      (node (ref "U$6") (pin "M1") (pinfunction "M1_M1") (pintype "bidirectional"))
    )
    (net (code "52") (name "Net-(JMP3-Pad2)") (class "Default")
      (node (ref "JMP3") (pin "2") (pinfunction "2_2") (pintype "passive"))
      (node (ref "U$6") (pin "M2") (pinfunction "M2_M2") (pintype "bidirectional"))
    )
    (net (code "53") (name "Net-(JMP4-Pad1)") (class "Default")
      (node (ref "JMP4") (pin "1") (pinfunction "1_1") (pintype "passive"))
      (node (ref "JMP5") (pin "1") (pinfunction "1_1") (pintype "passive"))
      (node (ref "JMP6") (pin "1") (pinfunction "1_1") (pintype "passive"))
      (node (ref "R11") (pin "1") (pinfunction "1_1") (pintype "passive"))
    )
    (net (code "54") (name "Net-(JMP4-Pad2)") (class "Default")
      (node (ref "JMP4") (pin "2") (pinfunction "2_2") (pintype "passive"))
      (node (ref "R12") (pin "1") (pinfunction "1_1") (pintype "passive"))
      (node (ref "U$7") (pin "M0") (pinfunction "M0_M0") (pintype "bidirectional"))
    )
    (net (code "55") (name "Net-(JMP5-Pad2)") (class "Default")
      (node (ref "JMP5") (pin "2") (pinfunction "2_2") (pintype "passive"))
      (node (ref "U$7") (pin "M1") (pinfunction "M1_M1") (pintype "bidirectional"))
    )
    (net (code "56") (name "Net-(JMP6-Pad2)") (class "Default")
      (node (ref "JMP6") (pin "2") (pinfunction "2_2") (pintype "passive"))
      (node (ref "U$7") (pin "M2") (pinfunction "M2_M2") (pintype "bidirectional"))
    )
    (net (code "57") (name "Net-(JP1-Pad1)") (class "Default")
      (node (ref "JP1") (pin "1") (pinfunction "1_1") (pintype "passive"))
      (node (ref "U$6") (pin "B2") (pinfunction "B2_B2") (pintype "bidirectional"))
    )
    (net (code "58") (name "Net-(JP1-Pad2)") (class "Default")
      (node (ref "JP1") (pin "2") (pinfunction "2_2") (pintype "passive"))
      (node (ref "U$6") (pin "B1") (pinfunction "B1_B1") (pintype "bidirectional"))
    )
    (net (code "59") (name "Net-(JP1-Pad3)") (class "Default")
      (node (ref "JP1") (pin "3") (pinfunction "3_3") (pintype "passive"))
      (node (ref "U$6") (pin "A1") (pinfunction "A1_A1") (pintype "bidirectional"))
    )
    (net (code "60") (name "Net-(JP1-Pad4)") (class "Default")
      (node (ref "JP1") (pin "4") (pinfunction "4_4") (pintype "passive"))
      (node (ref "U$6") (pin "A2") (pinfunction "A2_A2") (pintype "bidirectional"))
    )
    (net (code "61") (name "Net-(JP2-Pad1)") (class "Default")
      (node (ref "JP2") (pin "1") (pinfunction "1_1") (pintype "passive"))
      (node (ref "U$7") (pin "B2") (pinfunction "B2_B2") (pintype "bidirectional"))
    )
    (net (code "62") (name "Net-(JP2-Pad2)") (class "Default")
      (node (ref "JP2") (pin "2") (pinfunction "2_2") (pintype "passive"))
      (node (ref "U$7") (pin "B1") (pinfunction "B1_B1") (pintype "bidirectional"))
    )
    (net (code "63") (name "Net-(JP2-Pad3)") (class "Default")
      (node (ref "JP2") (pin "3") (pinfunction "3_3") (pintype "passive"))
      (node (ref "U$7") (pin "A1") (pinfunction "A1_A1") (pintype "bidirectional"))
    )
    (net (code "64") (name "Net-(JP2-Pad4)") (class "Default")
      (node (ref "JP2") (pin "4") (pinfunction "4_4") (pintype "passive"))
      (node (ref "U$7") (pin "A2") (pinfunction "A2_A2") (pintype "bidirectional"))
    )
    (net (code "65") (name "Net-(L1-1)") (class "Default")
      (node (ref "D1") (pin "C") (pinfunction "C_C") (pintype "passive"))
      (node (ref "L1") (pin "P$1") (pinfunction "1_P$1") (pintype "passive"))
      (node (ref "LM2594") (pin "8") (pinfunction "SW_8") (pintype "passive"))
    )
    (net (code "66") (name "Net-(L2-1)") (class "Default")
      (node (ref "L2") (pin "P$1") (pinfunction "1_P$1") (pintype "passive"))
      (node (ref "R4") (pin "2") (pinfunction "2_2") (pintype "passive"))
      (node (ref "U2") (pin "VBUS1") (pinfunction "VBUS_VBUS1") (pintype "bidirectional"))
    )
    (net (code "67") (name "Net-(L2-2)") (class "Default")
      (node (ref "C7") (pin "2") (pinfunction "2_2") (pintype "passive"))
      (node (ref "L2") (pin "P$2") (pinfunction "2_P$2") (pintype "passive"))
      (node (ref "LM2623") (pin "P$8") (pinfunction "SW_P$8") (pintype "bidirectional"))
      (node (ref "U$4") (pin "P$2") (pinfunction "P$2_P$2") (pintype "bidirectional"))
    )
    (net (code "68") (name "Net-(LM2594-VIN)") (class "Default")
      (node (ref "LM2594") (pin "7") (pinfunction "VIN_7") (pintype "power_in"))
      (node (ref "U$3") (pin "P$1") (pinfunction "C_P$1") (pintype "passive"))
    )
    (net (code "69") (name "Net-(LM2623-BOOT)") (class "Default")
      (node (ref "C9") (pin "1") (pinfunction "1_1") (pintype "passive"))
      (node (ref "LM2623") (pin "P$2") (pinfunction "EN_P$2") (pintype "bidirectional"))
      (node (ref "LM2623") (pin "P$6") (pinfunction "VDD_P$6") (pintype "bidirectional"))
      (node (ref "LM2623") (pin "P$7") (pinfunction "BOOT_P$7") (pintype "bidirectional"))
      (node (ref "R5") (pin "2") (pinfunction "2_2") (pintype "passive"))
      (node (ref "U$4") (pin "P$1") (pinfunction "P$1_P$1") (pintype "bidirectional"))
      (node (ref "U$5") (pin "P$2") (pinfunction "P$2_P$2") (pintype "bidirectional"))
    )
    (net (code "70") (name "Net-(LM2623-FB)") (class "Default")
      (node (ref "LM2623") (pin "P$4") (pinfunction "FB_P$4") (pintype "bidirectional"))
      (node (ref "R5") (pin "1") (pinfunction "1_1") (pintype "passive"))
      (node (ref "R6") (pin "2") (pinfunction "2_2") (pintype "passive"))
    )
    (net (code "71") (name "Net-(LM2623-FREQ)") (class "Default")
      (node (ref "C7") (pin "1") (pinfunction "1_1") (pintype "passive"))
      (node (ref "LM2623") (pin "P$3") (pinfunction "FREQ_P$3") (pintype "bidirectional"))
      (node (ref "R4") (pin "1") (pinfunction "1_1") (pintype "passive"))
    )
    (net (code "72") (name "Net-(R7-Pad1)") (class "Default")
      (node (ref "R7") (pin "1") (pinfunction "1_1") (pintype "passive"))
      (node (ref "U$6") (pin "RST") (pinfunction "RST_RST") (pintype "bidirectional"))
      (node (ref "U$6") (pin "SLP") (pinfunction "SLP_SLP") (pintype "bidirectional"))
    )
    (net (code "73") (name "Net-(R10-Pad1)") (class "Default")
      (node (ref "R10") (pin "1") (pinfunction "1_1") (pintype "passive"))
      (node (ref "U$7") (pin "RST") (pinfunction "RST_RST") (pintype "bidirectional"))
      (node (ref "U$7") (pin "SLP") (pinfunction "SLP_SLP") (pintype "bidirectional"))
    )
    (net (code "74") (name "Net-(U$2-IN1)") (class "Default")
      (node (ref "U$2") (pin "PIN") (pinfunction "IN1_PIN") (pintype "bidirectional"))
      (node (ref "VIN") (pin "2") (pinfunction "2_2") (pintype "passive"))
    )
    (net (code "75") (name "Net-(U$2-IN2)") (class "Default")
      (node (ref "U$2") (pin "PIN2") (pinfunction "IN2_PIN2") (pintype "bidirectional"))
      (node (ref "VIN") (pin "1") (pinfunction "1_1") (pintype "passive"))
    )
    (net (code "76") (name "Net-(U$8-D1A)") (class "Default")
      (node (ref "R14") (pin "2") (pinfunction "2_2") (pintype "passive"))
      (node (ref "U$8") (pin "1") (pinfunction "D1A_1") (pintype "bidirectional"))
    )
    (net (code "77") (name "Net-(U$8-D2A)") (class "Default")
      (node (ref "R13") (pin "2") (pinfunction "2_2") (pintype "passive"))
      (node (ref "U$8") (pin "3") (pinfunction "D2A_3") (pintype "bidirectional"))
    )
    (net (code "78") (name "Net-(U$8-OE1)") (class "Default")
      (node (ref "U$8") (pin "5") (pinfunction "OE2_5") (pintype "bidirectional"))
      (node (ref "U$8") (pin "7") (pinfunction "OE1_7") (pintype "bidirectional"))
      (node (ref "X2") (pin "2") (pinfunction "2_2") (pintype "passive"))
    )
    (net (code "79") (name "Net-(U$8-OK1)") (class "Default")
      (node (ref "U$8") (pin "8") (pinfunction "OK1_8") (pintype "bidirectional"))
      (node (ref "X2") (pin "3") (pinfunction "3_3") (pintype "passive"))
    )
    (net (code "80") (name "Net-(U$8-OK2)") (class "Default")
      (node (ref "U$8") (pin "6") (pinfunction "OK2_6") (pintype "bidirectional"))
      (node (ref "X2") (pin "1") (pinfunction "1_1") (pintype "passive"))
    )
    (net (code "81") (name "unconnected-(CP2102-CTS-Pad23)") (class "Default")
      (node (ref "CP2102") (pin "23") (pinfunction "CTS_23") (pintype "input"))
    )
    (net (code "82") (name "unconnected-(CP2102-DCD-Pad1)") (class "Default")
      (node (ref "CP2102") (pin "1") (pinfunction "DCD_1") (pintype "input"))
    )
    (net (code "83") (name "unconnected-(CP2102-DSR-Pad27)") (class "Default")
      (node (ref "CP2102") (pin "27") (pinfunction "DSR_27") (pintype "input"))
    )
    (net (code "84") (name "unconnected-(CP2102-RI-Pad2)") (class "Default")
      (node (ref "CP2102") (pin "2") (pinfunction "RI_2") (pintype "input"))
    )
    (net (code "85") (name "unconnected-(CP2102-RTS-Pad24)") (class "Default")
      (node (ref "CP2102") (pin "24") (pinfunction "RTS_24") (pintype "output"))
    )
    (net (code "86") (name "unconnected-(CP2102-SUSPEND-Pad12)") (class "Default")
      (node (ref "CP2102") (pin "12") (pinfunction "SUSPEND_12") (pintype "output"))
    )
    (net (code "87") (name "unconnected-(CP2102-~{SUSPEND}-Pad11)") (class "Default")
      (node (ref "CP2102") (pin "11") (pinfunction "~{SUSPEND}_11") (pintype "output"))
    )
    (net (code "88") (name "unconnected-(EXP1-Pad6)") (class "Default")
      (node (ref "EXP1") (pin "6") (pinfunction "6_6") (pintype "passive"))
    )
    (net (code "89") (name "unconnected-(EXP1-Pad7)") (class "Default")
      (node (ref "EXP1") (pin "7") (pinfunction "7_7") (pintype "passive"))
    )
    (net (code "90") (name "unconnected-(EXP1-Pad8)") (class "Default")
      (node (ref "EXP1") (pin "8") (pinfunction "8_8") (pintype "passive"))
    )
    (net (code "91") (name "unconnected-(EXP2-Pad1)") (class "Default")
      (node (ref "EXP2") (pin "1") (pinfunction "1_1") (pintype "passive"))
    )
    (net (code "92") (name "unconnected-(EXP2-Pad2)") (class "Default")
      (node (ref "EXP2") (pin "2") (pinfunction "2_2") (pintype "passive"))
    )
    (net (code "93") (name "unconnected-(EXP2-Pad4)") (class "Default")
      (node (ref "EXP2") (pin "4") (pinfunction "4_4") (pintype "passive"))
    )
    (net (code "94") (name "unconnected-(EXP2-Pad6)") (class "Default")
      (node (ref "EXP2") (pin "6") (pinfunction "6_6") (pintype "passive"))
    )
    (net (code "95") (name "unconnected-(EXP2-Pad7)") (class "Default")
      (node (ref "EXP2") (pin "7") (pinfunction "7_7") (pintype "passive"))
    )
    (net (code "96") (name "unconnected-(EXP2-Pad10)") (class "Default")
      (node (ref "EXP2") (pin "10") (pinfunction "10_10") (pintype "passive"))
    )
    (net (code "97") (name "unconnected-(IC1-(A9)PC1-Pad54)") (class "Default")
      (node (ref "IC1") (pin "54") (pinfunction "(A9)PC1_54") (pintype "bidirectional"))
    )
    (net (code "98") (name "unconnected-(IC1-(A11)PC3-Pad56)") (class "Default")
      (node (ref "IC1") (pin "56") (pinfunction "(A11)PC3_56") (pintype "bidirectional"))
    )
    (net (code "99") (name "unconnected-(IC1-(A12)PC4-Pad57)") (class "Default")
      (node (ref "IC1") (pin "57") (pinfunction "(A12)PC4_57") (pintype "bidirectional"))
    )
    (net (code "100") (name "unconnected-(IC1-(A14)PC6-Pad59)") (class "Default")
      (node (ref "IC1") (pin "59") (pinfunction "(A14)PC6_59") (pintype "bidirectional"))
    )
    (net (code "101") (name "unconnected-(IC1-(AD3)PA3-Pad75)") (class "Default")
      (node (ref "IC1") (pin "75") (pinfunction "(AD3)PA3_75") (pintype "bidirectional"))
    )
    (net (code "102") (name "unconnected-(IC1-(AD7)PA7-Pad71)") (class "Default")
      (node (ref "IC1") (pin "71") (pinfunction "(AD7)PA7_71") (pintype "bidirectional"))
    )
    (net (code "103") (name "unconnected-(IC1-(ADC0)PF0-Pad97)") (class "Default")
      (node (ref "IC1") (pin "97") (pinfunction "(ADC0)PF0_97") (pintype "bidirectional"))
    )
    (net (code "104") (name "unconnected-(IC1-(ADC1)PF1-Pad96)") (class "Default")
      (node (ref "IC1") (pin "96") (pinfunction "(ADC1)PF1_96") (pintype "bidirectional"))
    )
    (net (code "105") (name "unconnected-(IC1-(ADC2)PF2-Pad95)") (class "Default")
      (node (ref "IC1") (pin "95") (pinfunction "(ADC2)PF2_95") (pintype "bidirectional"))
    )
    (net (code "106") (name "unconnected-(IC1-(ADC3)PF3-Pad94)") (class "Default")
      (node (ref "IC1") (pin "94") (pinfunction "(ADC3)PF3_94") (pintype "bidirectional"))
    )
    (net (code "107") (name "unconnected-(IC1-(ADC4{slash}TCK)PF4-Pad93)") (class "Default")
      (node (ref "IC1") (pin "93") (pinfunction "(ADC4/TCK)PF4_93") (pintype "bidirectional"))
    )
    (net (code "108") (name "unconnected-(IC1-(ADC5{slash}TMS)PF5-Pad92)") (class "Default")
      (node (ref "IC1") (pin "92") (pinfunction "(ADC5/TMS)PF5_92") (pintype "bidirectional"))
    )
    (net (code "109") (name "unconnected-(IC1-(ADC6{slash}TDO)PF6-Pad91)") (class "Default")
      (node (ref "IC1") (pin "91") (pinfunction "(ADC6/TDO)PF6_91") (pintype "bidirectional"))
    )
    (net (code "110") (name "unconnected-(IC1-(ADC7{slash}TDI)PF7-Pad90)") (class "Default")
      (node (ref "IC1") (pin "90") (pinfunction "(ADC7/TDI)PF7_90") (pintype "bidirectional"))
    )
    (net (code "111") (name "unconnected-(IC1-(ALE)PG2-Pad70)") (class "Default")
      (node (ref "IC1") (pin "70") (pinfunction "(ALE)PG2_70") (pintype "bidirectional"))
    )
    (net (code "112") (name "unconnected-(IC1-(CLKO{slash}ICP3{slash}INT7)PE7-Pad9)") (class "Default")
      (node (ref "IC1") (pin "9") (pinfunction "(CLKO/ICP3/INT7)PE7_9") (pintype "bidirectional"))
    )
    (net (code "113") (name "unconnected-(IC1-(ICP1)PD4-Pad47)") (class "Default")
      (node (ref "IC1") (pin "47") (pinfunction "(ICP1)PD4_47") (pintype "bidirectional"))
    )
    (net (code "114") (name "unconnected-(IC1-(OC0A{slash}OC1C{slash}PCINT7)PB7-Pad26)") (class "Default")
      (node (ref "IC1") (pin "26") (pinfunction "(OC0A/OC1C/PCINT7)PB7_26") (pintype "bidirectional"))
    )
    (net (code "115") (name "unconnected-(IC1-(OC0B)PG5-Pad1)") (class "Default")
      (node (ref "IC1") (pin "1") (pinfunction "(OC0B)PG5_1") (pintype "bidirectional"))
    )
    (net (code "116") (name "unconnected-(IC1-(OC1A{slash}PCINT5)PB5-Pad24)") (class "Default")
      (node (ref "IC1") (pin "24") (pinfunction "(OC1A/PCINT5)PB5_24") (pintype "bidirectional"))
    )
    (net (code "117") (name "unconnected-(IC1-(OC1B{slash}PCINT6)PB6-Pad25)") (class "Default")
      (node (ref "IC1") (pin "25") (pinfunction "(OC1B/PCINT6)PB6_25") (pintype "bidirectional"))
    )
    (net (code "118") (name "unconnected-(IC1-(OC2A{slash}PCINT4)PB4-Pad23)") (class "Default")
      (node (ref "IC1") (pin "23") (pinfunction "(OC2A/PCINT4)PB4_23") (pintype "bidirectional"))
    )
    (net (code "119") (name "unconnected-(IC1-(OC3A{slash}AIN1)PE3-Pad5)") (class "Default")
      (node (ref "IC1") (pin "5") (pinfunction "(OC3A/AIN1)PE3_5") (pintype "bidirectional"))
    )
    (net (code "120") (name "unconnected-(IC1-(OC3B{slash}INT4)PE4-Pad6)") (class "Default")
      (node (ref "IC1") (pin "6") (pinfunction "(OC3B/INT4)PE4_6") (pintype "bidirectional"))
    )
    (net (code "121") (name "unconnected-(IC1-(OC3C{slash}INT5)PE5-Pad7)") (class "Default")
      (node (ref "IC1") (pin "7") (pinfunction "(OC3C/INT5)PE5_7") (pintype "bidirectional"))
    )
    (net (code "122") (name "unconnected-(IC1-(RD)PG1-Pad52)") (class "Default")
      (node (ref "IC1") (pin "52") (pinfunction "(RD)PG1_52") (pintype "bidirectional"))
    )
    (net (code "123") (name "unconnected-(IC1-(T0)PD7-Pad50)") (class "Default")
      (node (ref "IC1") (pin "50") (pinfunction "(T0)PD7_50") (pintype "bidirectional"))
    )
    (net (code "124") (name "unconnected-(IC1-(T3{slash}INT6)PE6-Pad8)") (class "Default")
      (node (ref "IC1") (pin "8") (pinfunction "(T3/INT6)PE6_8") (pintype "bidirectional"))
    )
    (net (code "125") (name "unconnected-(IC1-(TOSC1)PG4-Pad29)") (class "Default")
      (node (ref "IC1") (pin "29") (pinfunction "(TOSC1)PG4_29") (pintype "bidirectional"))
    )
    (net (code "126") (name "unconnected-(IC1-(TOSC2)PG3-Pad28)") (class "Default")
      (node (ref "IC1") (pin "28") (pinfunction "(TOSC2)PG3_28") (pintype "bidirectional"))
    )
    (net (code "127") (name "unconnected-(IC1-(WR)PG0-Pad51)") (class "Default")
      (node (ref "IC1") (pin "51") (pinfunction "(WR)PG0_51") (pintype "bidirectional"))
    )
    (net (code "128") (name "unconnected-(IC1-(XCK0{slash}AIN0)PE2-Pad4)") (class "Default")
      (node (ref "IC1") (pin "4") (pinfunction "(XCK0/AIN0)PE2_4") (pintype "bidirectional"))
    )
    (net (code "129") (name "unconnected-(IC1-(XCK1)PD5-Pad48)") (class "Default")
      (node (ref "IC1") (pin "48") (pinfunction "(XCK1)PD5_48") (pintype "bidirectional"))
    )
    (net (code "130") (name "unconnected-(IC1-AREF-Pad98)") (class "Default")
      (node (ref "IC1") (pin "98") (pinfunction "AREF_98") (pintype "bidirectional"))
    )
    (net (code "131") (name "unconnected-(IC1-PH2(XCK2)-Pad14)") (class "Default")
      (node (ref "IC1") (pin "14") (pinfunction "PH2(XCK2)_14") (pintype "bidirectional"))
    )
    (net (code "132") (name "unconnected-(IC1-PH3(OC4A)-Pad15)") (class "Default")
      (node (ref "IC1") (pin "15") (pinfunction "PH3(OC4A)_15") (pintype "bidirectional"))
    )
    (net (code "133") (name "unconnected-(IC1-PH4(OC4B)-Pad16)") (class "Default")
      (node (ref "IC1") (pin "16") (pinfunction "PH4(OC4B)_16") (pintype "bidirectional"))
    )
    (net (code "134") (name "unconnected-(IC1-PH5(OC4C)-Pad17)") (class "Default")
      (node (ref "IC1") (pin "17") (pinfunction "PH5(OC4C)_17") (pintype "bidirectional"))
    )
    (net (code "135") (name "unconnected-(IC1-PH6(OC2B)-Pad18)") (class "Default")
      (node (ref "IC1") (pin "18") (pinfunction "PH6(OC2B)_18") (pintype "bidirectional"))
    )
    (net (code "136") (name "unconnected-(IC1-PH7(T4)-Pad27)") (class "Default")
      (node (ref "IC1") (pin "27") (pinfunction "PH7(T4)_27") (pintype "bidirectional"))
    )
    (net (code "137") (name "unconnected-(IC1-PJ2(XCK3{slash}PCINT11)-Pad65)") (class "Default")
      (node (ref "IC1") (pin "65") (pinfunction "PJ2(XCK3/PCINT11)_65") (pintype "bidirectional"))
    )
    (net (code "138") (name "unconnected-(IC1-PJ3(PCINT12)-Pad66)") (class "Default")
      (node (ref "IC1") (pin "66") (pinfunction "PJ3(PCINT12)_66") (pintype "bidirectional"))
    )
    (net (code "139") (name "unconnected-(IC1-PJ4(PCINT13)-Pad67)") (class "Default")
      (node (ref "IC1") (pin "67") (pinfunction "PJ4(PCINT13)_67") (pintype "bidirectional"))
    )
    (net (code "140") (name "unconnected-(IC1-PJ5(PCINT14)-Pad68)") (class "Default")
      (node (ref "IC1") (pin "68") (pinfunction "PJ5(PCINT14)_68") (pintype "bidirectional"))
    )
    (net (code "141") (name "unconnected-(IC1-PJ6(PCINT15)-Pad69)") (class "Default")
      (node (ref "IC1") (pin "69") (pinfunction "PJ6(PCINT15)_69") (pintype "bidirectional"))
    )
    (net (code "142") (name "unconnected-(IC1-PJ7-Pad79)") (class "Default")
      (node (ref "IC1") (pin "79") (pinfunction "PJ7_79") (pintype "bidirectional"))
    )
    (net (code "143") (name "unconnected-(IC1-PK2(ADC10{slash}PCINT18)-Pad87)") (class "Default")
      (node (ref "IC1") (pin "87") (pinfunction "PK2(ADC10/PCINT18)_87") (pintype "bidirectional"))
    )
    (net (code "144") (name "unconnected-(IC1-PK3(ADC11{slash}PCINT19)-Pad86)") (class "Default")
      (node (ref "IC1") (pin "86") (pinfunction "PK3(ADC11/PCINT19)_86") (pintype "bidirectional"))
    )
    (net (code "145") (name "unconnected-(IC1-PK4(ADC12{slash}PCINT20)-Pad85)") (class "Default")
      (node (ref "IC1") (pin "85") (pinfunction "PK4(ADC12/PCINT20)_85") (pintype "bidirectional"))
    )
    (net (code "146") (name "unconnected-(IC1-PK5(ADC13{slash}PCINT21)-Pad84)") (class "Default")
      (node (ref "IC1") (pin "84") (pinfunction "PK5(ADC13/PCINT21)_84") (pintype "bidirectional"))
    )
    (net (code "147") (name "unconnected-(IC1-PK6(ADC14{slash}PCINT22)-Pad83)") (class "Default")
      (node (ref "IC1") (pin "83") (pinfunction "PK6(ADC14/PCINT22)_83") (pintype "bidirectional"))
    )
    (net (code "148") (name "unconnected-(IC1-PL1(ICP5)-Pad36)") (class "Default")
      (node (ref "IC1") (pin "36") (pinfunction "PL1(ICP5)_36") (pintype "bidirectional"))
    )
    (net (code "149") (name "unconnected-(IC1-PL2(T5)-Pad37)") (class "Default")
      (node (ref "IC1") (pin "37") (pinfunction "PL2(T5)_37") (pintype "bidirectional"))
    )
    (net (code "150") (name "unconnected-(IC1-PL4(OC5B)-Pad39)") (class "Default")
      (node (ref "IC1") (pin "39") (pinfunction "PL4(OC5B)_39") (pintype "bidirectional"))
    )
    (net (code "151") (name "unconnected-(IC1-PL7-Pad42)") (class "Default")
      (node (ref "IC1") (pin "42") (pinfunction "PL7_42") (pintype "bidirectional"))
    )
    (net (code "152") (name "unconnected-(ISP-Pad8)") (class "Default")
      (node (ref "ISP") (pin "8") (pinfunction "8_8") (pintype "passive"))
    )
    (net (code "153") (name "unconnected-(S1-P1-Pad4)") (class "Default")
      (node (ref "S1") (pin "4") (pinfunction "P1_4") (pintype "passive"))
    )
    (net (code "154") (name "unconnected-(S1-S1-Pad2)") (class "Default")
      (node (ref "S1") (pin "2") (pinfunction "S1_2") (pintype "passive"))
    )
    (net (code "155") (name "unconnected-(U1-USBID-PadID1)") (class "Default")
      (node (ref "U1") (pin "ID1") (pinfunction "USBID_ID1") (pintype "bidirectional"))
    )
    (net (code "156") (name "unconnected-(U2-D+-PadD+1)") (class "Default")
      (node (ref "U2") (pin "D+1") (pinfunction "D+_D+1") (pintype "bidirectional"))
    )
    (net (code "157") (name "unconnected-(U2-D--PadD-1)") (class "Default")
      (node (ref "U2") (pin "D-1") (pinfunction "D-_D-1") (pintype "bidirectional"))
    )
    (net (code "158") (name "unconnected-(U2-USBID-PadID1)") (class "Default")
      (node (ref "U2") (pin "ID1") (pinfunction "USBID_ID1") (pintype "bidirectional"))
    )
    (net (code "159") (name "unconnected-(X2-2-Pad2@2)") (class "Default")
      (node (ref "X2") (pin "2@2") (pinfunction "2_2@2") (pintype "passive"))
    )
  )
)
